# IEEE_REC_Audio_Amplifier.net
KiCad netlist of a schematic drawn in EAGLE
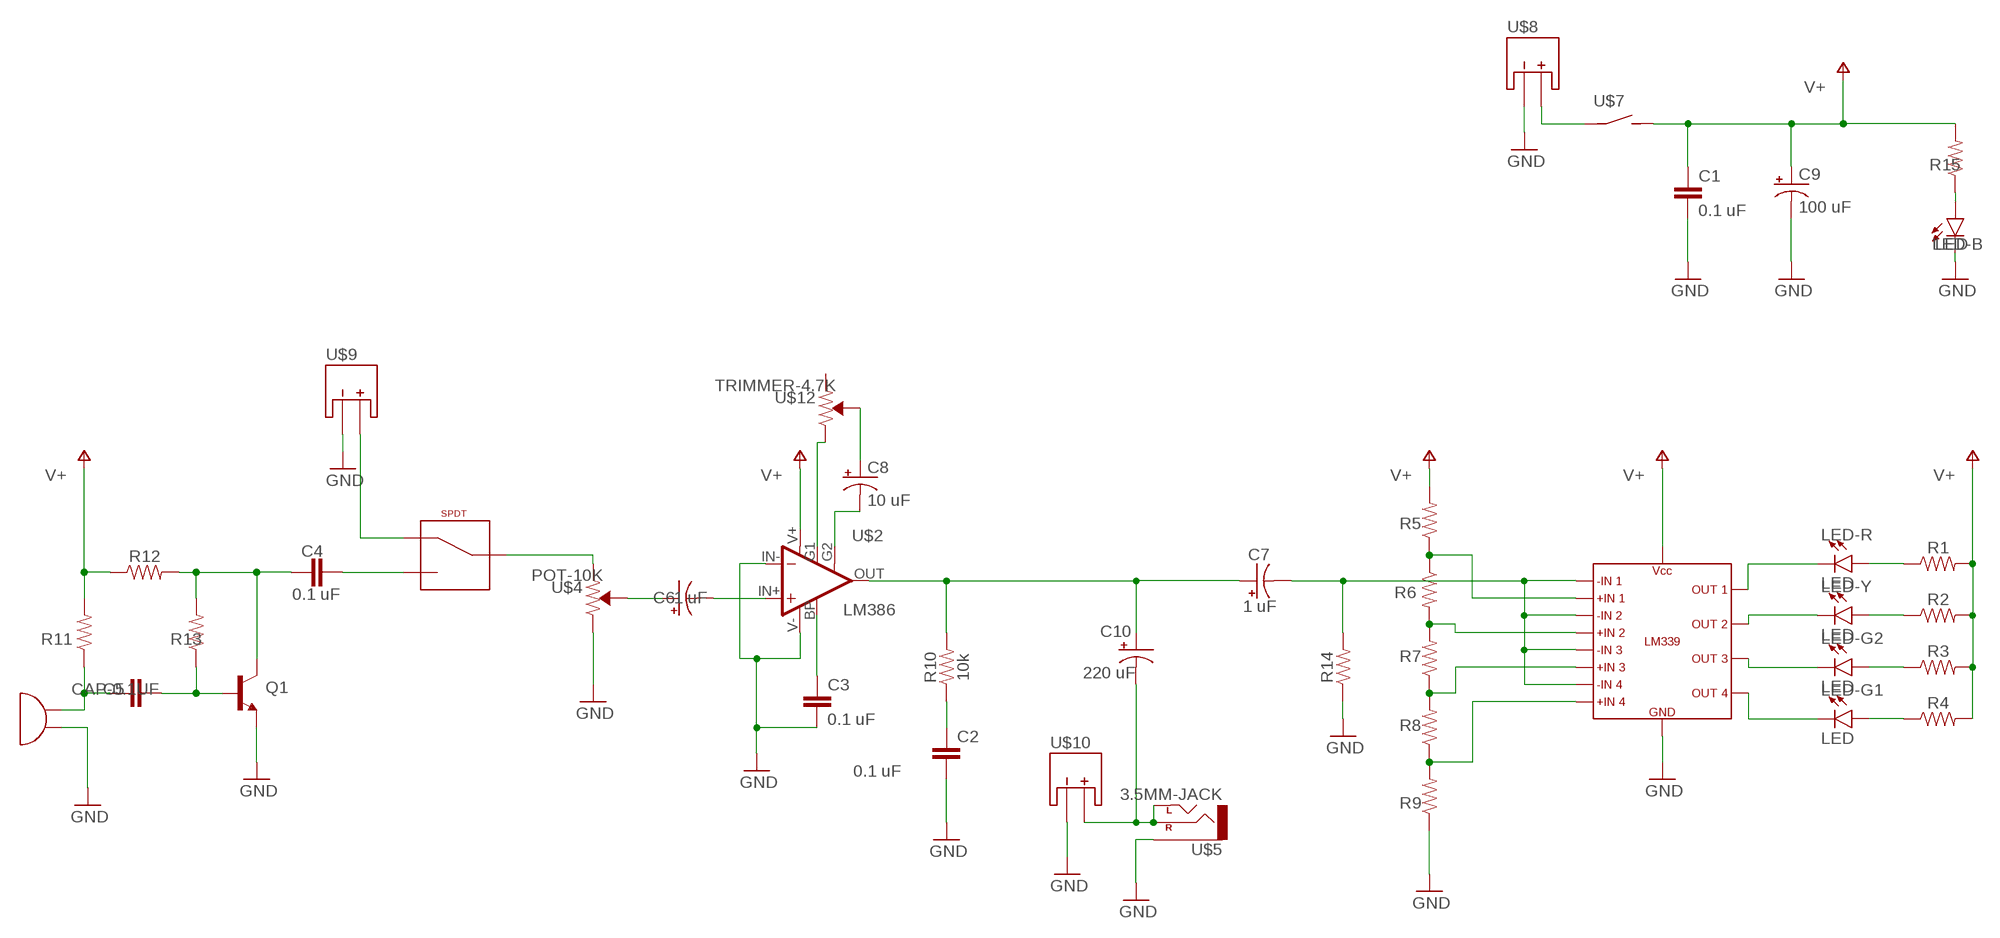
[diagram p0: schematic, sheet 1]

(export (version "E")
  (design (tool "Eeschema 10.0.6"))
  (components
    (comp (ref "C1")
      (value "0.1 uF")
      (footprint "eagle-import:CAP-PTH-SMALL-KIT")
      (libsource (lib "eagle-import") (part "CAP-0.1UF"))
    )
    (comp (ref "C2")
      (value "0.1 uF")
      (footprint "eagle-import:CAP-PTH-SMALL-KIT")
      (libsource (lib "eagle-import") (part "CAP-0.1UF"))
    )
    (comp (ref "C3")
      (value "0.1 uF")
      (footprint "eagle-import:CAP-PTH-SMALL-KIT")
      (libsource (lib "eagle-import") (part "CAP-0.1UF"))
    )
    (comp (ref "C4")
      (value "0.1 uF")
      (footprint "eagle-import:CAP-PTH-SMALL-KIT")
      (libsource (lib "eagle-import") (part "CAP-0.1UF"))
    )
    (comp (ref "C5")
      (value "CAP-0.1UF")
      (footprint "eagle-import:CAP-PTH-SMALL-KIT")
      (libsource (lib "eagle-import") (part "CAP-0.1UF"))
    )
    (comp (ref "C6")
      (value "1 uF")
      (footprint "eagle-import:CPOL-RADIAL-2.5MM-5.2MM")
      (libsource (lib "eagle-import") (part "CAP-1UF"))
    )
    (comp (ref "C7")
      (value "1 uF")
      (footprint "eagle-import:CPOL-RADIAL-2.5MM-5.2MM")
      (libsource (lib "eagle-import") (part "CAP-1UF"))
    )
    (comp (ref "C8")
      (value "10 uF")
      (footprint "eagle-import:CPOL-RADIAL-2.5MM-5.2MM")
      (libsource (lib "eagle-import") (part "CAP-10UF"))
    )
    (comp (ref "C9")
      (value "100 uF")
      (footprint "eagle-import:CPOL-RADIAL-2.5MM-6.5MM")
      (libsource (lib "eagle-import") (part "CAP-100UF"))
    )
    (comp (ref "C10")
      (value "220 uF")
      (footprint "eagle-import:CPOL-RADIAL-2.5MM-8.1MM")
      (libsource (lib "eagle-import") (part "CAP-220UF"))
    )
    (comp (ref "LED-B")
      (value "LED")
      (footprint "eagle-import:LED_5MM-KIT")
      (libsource (lib "eagle-import") (part "LED"))
    )
    (comp (ref "LED-G1")
      (value "LED")
      (footprint "eagle-import:LED_5MM-KIT")
      (libsource (lib "eagle-import") (part "LED"))
    )
    (comp (ref "LED-G2")
      (value "LED")
      (footprint "eagle-import:LED_5MM-KIT")
      (libsource (lib "eagle-import") (part "LED"))
    )
    (comp (ref "LED-R")
      (value "LED")
      (footprint "eagle-import:LED_5MM-KIT")
      (libsource (lib "eagle-import") (part "LED"))
    )
    (comp (ref "LED-Y")
      (value "LED")
      (footprint "eagle-import:LED_5MM-KIT")
      (libsource (lib "eagle-import") (part "LED"))
    )
    (comp (ref "Q1")
      (value "2N3904")
      (footprint "eagle-import:TO92-CBE")
      (libsource (lib "eagle-import") (part "2N3904"))
    )
    (comp (ref "R1")
      (value "470")
      (footprint "eagle-import:AXIAL-0.3-KIT")
      (libsource (lib "eagle-import") (part "RESISTOR"))
    )
    (comp (ref "R2")
      (value "RESISTOR")
      (footprint "eagle-import:AXIAL-0.3-KIT")
      (libsource (lib "eagle-import") (part "RESISTOR"))
    )
    (comp (ref "R3")
      (value "RESISTOR")
      (footprint "eagle-import:AXIAL-0.3-KIT")
      (libsource (lib "eagle-import") (part "RESISTOR"))
    )
    (comp (ref "R4")
      (value "RESISTOR")
      (footprint "eagle-import:AXIAL-0.3-KIT")
      (libsource (lib "eagle-import") (part "RESISTOR"))
    )
    (comp (ref "R5")
      (value "RESISTOR")
      (footprint "eagle-import:AXIAL-0.3-KIT")
      (libsource (lib "eagle-import") (part "RESISTOR"))
    )
    (comp (ref "R6")
      (value "RESISTOR")
      (footprint "eagle-import:AXIAL-0.3-KIT")
      (libsource (lib "eagle-import") (part "RESISTOR"))
    )
    (comp (ref "R7")
      (value "RESISTOR")
      (footprint "eagle-import:AXIAL-0.3-KIT")
      (libsource (lib "eagle-import") (part "RESISTOR"))
    )
    (comp (ref "R8")
      (value "RESISTOR")
      (footprint "eagle-import:AXIAL-0.3-KIT")
      (libsource (lib "eagle-import") (part "RESISTOR"))
    )
    (comp (ref "R9")
      (value "RESISTOR")
      (footprint "eagle-import:AXIAL-0.3-KIT")
      (libsource (lib "eagle-import") (part "RESISTOR"))
    )
    (comp (ref "R10")
      (value "10k")
      (footprint "eagle-import:AXIAL-0.3-KIT")
      (libsource (lib "eagle-import") (part "RESISTOR"))
    )
    (comp (ref "R11")
      (value "RESISTOR")
      (footprint "eagle-import:AXIAL-0.3-KIT")
      (libsource (lib "eagle-import") (part "RESISTOR"))
    )
    (comp (ref "R12")
      (value "RESISTOR")
      (footprint "eagle-import:AXIAL-0.3-KIT")
      (libsource (lib "eagle-import") (part "RESISTOR"))
    )
    (comp (ref "R13")
      (value "RESISTOR")
      (footprint "eagle-import:AXIAL-0.3-KIT")
      (libsource (lib "eagle-import") (part "RESISTOR"))
    )
    (comp (ref "R14")
      (value "RESISTOR")
      (footprint "eagle-import:AXIAL-0.3-KIT")
      (libsource (lib "eagle-import") (part "RESISTOR"))
    )
    (comp (ref "R15")
      (value "RESISTOR")
      (footprint "eagle-import:AXIAL-0.3-KIT")
      (libsource (lib "eagle-import") (part "RESISTOR"))
    )
    (comp (ref "U$1")
      (value "SPDT")
      (footprint "eagle-import:OS102011MA1QN1")
      (libsource (lib "eagle-import") (part "SPDT"))
    )
    (comp (ref "U$2")
      (value "LM386")
      (footprint "eagle-import:DIL08")
      (libsource (lib "eagle-import") (part "LM386"))
    )
    (comp (ref "U$3")
      (value "LM339")
      (footprint "eagle-import:DIL14")
      (libsource (lib "eagle-import") (part "LM339"))
    )
    (comp (ref "U$4")
      (value "POT-10K")
      (footprint "eagle-import:PTV09-SERIES")
      (libsource (lib "eagle-import") (part "POT-10K"))
    )
    (comp (ref "U$5")
      (value "3.5MM-JACK")
      (footprint "eagle-import:SJ1-352XN")
      (libsource (lib "eagle-import") (part "3.5MM-JACK"))
    )
    (comp (ref "U$6")
      (value "MIC")
      (footprint "eagle-import:MIC")
      (libsource (lib "eagle-import") (part "MIC"))
    )
    (comp (ref "U$7")
      (value "SPST")
      (footprint "eagle-import:TMS6T1B1M1QE")
      (libsource (lib "eagle-import") (part "SPST"))
    )
    (comp (ref "U$8")
      (value "2PIN-CONNECTOR")
      (footprint "eagle-import:2PIN-CONN")
      (libsource (lib "eagle-import") (part "2PIN-CONNECTOR"))
    )
    (comp (ref "U$9")
      (value "2PIN-CONNECTOR")
      (footprint "eagle-import:2PIN-CONN")
      (libsource (lib "eagle-import") (part "2PIN-CONNECTOR"))
    )
    (comp (ref "U$10")
      (value "2PIN-CONNECTOR")
      (footprint "eagle-import:2PIN-CONN")
      (libsource (lib "eagle-import") (part "2PIN-CONNECTOR"))
    )
    (comp (ref "U$12")
      (value "TRIMMER-4.7K")
      (footprint "eagle-import:CB10MV472ME")
      (libsource (lib "eagle-import") (part "TRIMMER-4.7K"))
    )
  )
  (nets
    (net (code "1") (name "GND") (class "Default")
      (node (ref "C1") (pin "2") (pinfunction "2_2") (pintype "passive"))
      (node (ref "C2") (pin "2") (pinfunction "2_2") (pintype "passive"))
      (node (ref "C3") (pin "2") (pinfunction "2_2") (pintype "passive"))
      (node (ref "C9") (pin "-") (pinfunction "-_-") (pintype "passive"))
      (node (ref "LED-B") (pin "-") (pinfunction "C_-") (pintype "passive"))
      (node (ref "Q1") (pin "E") (pinfunction "E_E") (pintype "passive"))
      (node (ref "R14") (pin "P$1") (pinfunction "1_P$1") (pintype "passive"))
      (node (ref "R9") (pin "P$1") (pinfunction "1_P$1") (pintype "passive"))
      (node (ref "U$10") (pin "-") (pinfunction "-_-") (pintype "bidirectional"))
      (node (ref "U$2") (pin "IN-") (pinfunction "-IN_IN-") (pintype "input"))
      (node (ref "U$2") (pin "V-") (pinfunction "V-_V-") (pintype "power_in"))
      (node (ref "U$3") (pin "P$12") (pinfunction "P12_P$12") (pintype "bidirectional"))
      (node (ref "U$4") (pin "P$3") (pinfunction "CW_P$3") (pintype "passive"))
      (node (ref "U$5") (pin "P$1") (pinfunction "SLEEVE_P$1") (pintype "bidirectional"))
      (node (ref "U$6") (pin "-") (pinfunction "P$1_-") (pintype "bidirectional"))
      (node (ref "U$8") (pin "-") (pinfunction "-_-") (pintype "bidirectional"))
      (node (ref "U$9") (pin "-") (pinfunction "-_-") (pintype "bidirectional"))
    )
    (net (code "2") (name "Net-(C3-Pad1)") (class "Default")
      (node (ref "C3") (pin "1") (pinfunction "1_1") (pintype "passive"))
      (node (ref "U$2") (pin "BP") (pinfunction "BP_BP") (pintype "bidirectional"))
    )
    (net (code "3") (name "Net-(C4-Pad2)") (class "Default")
      (node (ref "C4") (pin "2") (pinfunction "2_2") (pintype "passive"))
      (node (ref "U$1") (pin "P$3") (pinfunction "P$3_P$3") (pintype "bidirectional"))
    )
    (net (code "4") (name "Net-(C8-Pad-)") (class "Default")
      (node (ref "C8") (pin "-") (pinfunction "-_-") (pintype "passive"))
      (node (ref "U$2") (pin "G2") (pinfunction "GAIN_G2") (pintype "bidirectional"))
    )
    (net (code "5") (name "Net-(LED-B-A)") (class "Default")
      (node (ref "LED-B") (pin "+") (pinfunction "A_+") (pintype "passive"))
      (node (ref "R15") (pin "P$1") (pinfunction "1_P$1") (pintype "passive"))
    )
    (net (code "6") (name "Net-(LED-G1-A)") (class "Default")
      (node (ref "LED-G1") (pin "+") (pinfunction "A_+") (pintype "passive"))
      (node (ref "R4") (pin "P$1") (pinfunction "1_P$1") (pintype "passive"))
    )
    (net (code "7") (name "Net-(LED-G1-C)") (class "Default")
      (node (ref "LED-G1") (pin "-") (pinfunction "C_-") (pintype "passive"))
      (node (ref "U$3") (pin "P$13") (pinfunction "P13_P$13") (pintype "bidirectional"))
    )
    (net (code "8") (name "Net-(LED-G2-A)") (class "Default")
      (node (ref "LED-G2") (pin "+") (pinfunction "A_+") (pintype "passive"))
      (node (ref "R3") (pin "P$1") (pinfunction "1_P$1") (pintype "passive"))
    )
    (net (code "9") (name "Net-(LED-G2-C)") (class "Default")
      (node (ref "LED-G2") (pin "-") (pinfunction "C_-") (pintype "passive"))
      (node (ref "U$3") (pin "P$14") (pinfunction "P14_P$14") (pintype "bidirectional"))
    )
    (net (code "10") (name "Net-(LED-R-A)") (class "Default")
      (node (ref "LED-R") (pin "+") (pinfunction "A_+") (pintype "passive"))
      (node (ref "R1") (pin "P$1") (pinfunction "1_P$1") (pintype "passive"))
    )
    (net (code "11") (name "Net-(LED-R-C)") (class "Default")
      (node (ref "LED-R") (pin "-") (pinfunction "C_-") (pintype "passive"))
      (node (ref "U$3") (pin "P$1") (pinfunction "P1_P$1") (pintype "bidirectional"))
    )
    (net (code "12") (name "Net-(LED-Y-A)") (class "Default")
      (node (ref "LED-Y") (pin "+") (pinfunction "A_+") (pintype "passive"))
      (node (ref "R2") (pin "P$1") (pinfunction "1_P$1") (pintype "passive"))
    )
    (net (code "13") (name "Net-(LED-Y-C)") (class "Default")
      (node (ref "LED-Y") (pin "-") (pinfunction "C_-") (pintype "passive"))
      (node (ref "U$3") (pin "P$2") (pinfunction "P2_P$2") (pintype "bidirectional"))
    )
    (net (code "14") (name "Net-(R5-1)") (class "Default")
      (node (ref "R5") (pin "P$1") (pinfunction "1_P$1") (pintype "passive"))
      (node (ref "R6") (pin "P$1") (pinfunction "1_P$1") (pintype "passive"))
      (node (ref "U$3") (pin "P$7") (pinfunction "P7_P$7") (pintype "bidirectional"))
    )
    (net (code "15") (name "Net-(R6-2)") (class "Default")
      (node (ref "R6") (pin "P$2") (pinfunction "2_P$2") (pintype "passive"))
      (node (ref "R7") (pin "P$2") (pinfunction "2_P$2") (pintype "passive"))
      (node (ref "U$3") (pin "P$5") (pinfunction "P5_P$5") (pintype "bidirectional"))
    )
    (net (code "16") (name "Net-(R7-1)") (class "Default")
      (node (ref "R7") (pin "P$1") (pinfunction "1_P$1") (pintype "passive"))
      (node (ref "R8") (pin "P$2") (pinfunction "2_P$2") (pintype "passive"))
      (node (ref "U$3") (pin "P$9") (pinfunction "P9_P$9") (pintype "bidirectional"))
    )
    (net (code "17") (name "Net-(R8-1)") (class "Default")
      (node (ref "R8") (pin "P$1") (pinfunction "1_P$1") (pintype "passive"))
      (node (ref "R9") (pin "P$2") (pinfunction "2_P$2") (pintype "passive"))
      (node (ref "U$3") (pin "P$11") (pinfunction "P11_P$11") (pintype "bidirectional"))
    )
    (net (code "18") (name "Net-(R10-1)") (class "Default")
      (node (ref "C2") (pin "1") (pinfunction "1_1") (pintype "passive"))
      (node (ref "R10") (pin "P$1") (pinfunction "1_P$1") (pintype "passive"))
    )
    (net (code "19") (name "Net-(R10-2)") (class "Default")
      (node (ref "C10") (pin "+") (pinfunction "+_+") (pintype "passive"))
      (node (ref "C7") (pin "+") (pinfunction "+_+") (pintype "passive"))
      (node (ref "R10") (pin "P$2") (pinfunction "2_P$2") (pintype "passive"))
      (node (ref "U$2") (pin "OUT") (pinfunction "OUT_OUT") (pintype "output"))
    )
    (net (code "20") (name "Net-(R11-1)") (class "Default")
      (node (ref "C5") (pin "1") (pinfunction "1_1") (pintype "passive"))
      (node (ref "R11") (pin "P$1") (pinfunction "1_P$1") (pintype "passive"))
      (node (ref "U$6") (pin "+") (pinfunction "P$2_+") (pintype "bidirectional"))
    )
    (net (code "21") (name "Net-(R12-2)") (class "Default")
      (node (ref "C4") (pin "1") (pinfunction "1_1") (pintype "passive"))
      (node (ref "Q1") (pin "C") (pinfunction "C_C") (pintype "passive"))
      (node (ref "R12") (pin "P$2") (pinfunction "2_P$2") (pintype "passive"))
      (node (ref "R13") (pin "P$2") (pinfunction "2_P$2") (pintype "passive"))
    )
    (net (code "22") (name "Net-(R13-1)") (class "Default")
      (node (ref "C5") (pin "2") (pinfunction "2_2") (pintype "passive"))
      (node (ref "Q1") (pin "B") (pinfunction "B_B") (pintype "passive"))
      (node (ref "R13") (pin "P$1") (pinfunction "1_P$1") (pintype "passive"))
    )
    (net (code "23") (name "Net-(R14-2)") (class "Default")
      (node (ref "C7") (pin "-") (pinfunction "-_-") (pintype "passive"))
      (node (ref "R14") (pin "P$2") (pinfunction "2_P$2") (pintype "passive"))
      (node (ref "U$3") (pin "P$10") (pinfunction "P10_P$10") (pintype "bidirectional"))
      (node (ref "U$3") (pin "P$4") (pinfunction "P4_P$4") (pintype "bidirectional"))
      (node (ref "U$3") (pin "P$6") (pinfunction "P6_P$6") (pintype "bidirectional"))
      (node (ref "U$3") (pin "P$8") (pinfunction "P8_P$8") (pintype "bidirectional"))
    )
    (net (code "24") (name "Net-(U$1-PadP$1)") (class "Default")
      (node (ref "U$1") (pin "P$1") (pinfunction "P$1_P$1") (pintype "bidirectional"))
      (node (ref "U$9") (pin "+") (pinfunction "+_+") (pintype "bidirectional"))
    )
    (net (code "25") (name "Net-(U$2-+IN)") (class "Default")
      (node (ref "C6") (pin "-") (pinfunction "-_-") (pintype "passive"))
      (node (ref "U$2") (pin "IN+") (pinfunction "+IN_IN+") (pintype "input"))
    )
    (net (code "26") (name "Net-(U$4-CCW)") (class "Default")
      (node (ref "U$1") (pin "P$2") (pinfunction "P$2_P$2") (pintype "bidirectional"))
      (node (ref "U$4") (pin "P$1") (pinfunction "CCW_P$1") (pintype "passive"))
    )
    (net (code "27") (name "Net-(U$4-WIPER)") (class "Default")
      (node (ref "C6") (pin "+") (pinfunction "+_+") (pintype "passive"))
      (node (ref "U$4") (pin "P$2") (pinfunction "WIPER_P$2") (pintype "passive"))
    )
    (net (code "28") (name "Net-(U$5-LEFT)") (class "Default")
      (node (ref "C10") (pin "-") (pinfunction "-_-") (pintype "passive"))
      (node (ref "U$10") (pin "+") (pinfunction "+_+") (pintype "bidirectional"))
      (node (ref "U$5") (pin "P$2") (pinfunction "RIGHT_P$2") (pintype "bidirectional"))
      (node (ref "U$5") (pin "P$3") (pinfunction "LEFT_P$3") (pintype "bidirectional"))
    )
    (net (code "29") (name "Net-(U$7-P)") (class "Default")
      (node (ref "U$7") (pin "+") (pinfunction "P_+") (pintype "passive"))
      (node (ref "U$8") (pin "+") (pinfunction "+_+") (pintype "bidirectional"))
    )
    (net (code "30") (name "Net-(U$12-CW)") (class "Default")
      (node (ref "U$12") (pin "P$3") (pinfunction "CW_P$3") (pintype "passive"))
      (node (ref "U$2") (pin "G1") (pinfunction "GAIN_G1") (pintype "bidirectional"))
    )
    (net (code "31") (name "Net-(U$12-WIPER)") (class "Default")
      (node (ref "C8") (pin "+") (pinfunction "+_+") (pintype "passive"))
      (node (ref "U$12") (pin "P$2") (pinfunction "WIPER_P$2") (pintype "passive"))
    )
    (net (code "32") (name "V+") (class "Default")
      (node (ref "C1") (pin "1") (pinfunction "1_1") (pintype "passive"))
      (node (ref "C9") (pin "+") (pinfunction "+_+") (pintype "passive"))
      (node (ref "R1") (pin "P$2") (pinfunction "2_P$2") (pintype "passive"))
      (node (ref "R11") (pin "P$2") (pinfunction "2_P$2") (pintype "passive"))
      (node (ref "R12") (pin "P$1") (pinfunction "1_P$1") (pintype "passive"))
      (node (ref "R15") (pin "P$2") (pinfunction "2_P$2") (pintype "passive"))
      (node (ref "R2") (pin "P$2") (pinfunction "2_P$2") (pintype "passive"))
      (node (ref "R3") (pin "P$2") (pinfunction "2_P$2") (pintype "passive"))
      (node (ref "R4") (pin "P$2") (pinfunction "2_P$2") (pintype "passive"))
      (node (ref "R5") (pin "P$2") (pinfunction "2_P$2") (pintype "passive"))
      (node (ref "U$2") (pin "V+") (pinfunction "V+_V+") (pintype "power_in"))
      (node (ref "U$3") (pin "P$3") (pinfunction "P3_P$3") (pintype "bidirectional"))
      (node (ref "U$7") (pin "-") (pinfunction "S_-") (pintype "passive"))
    )
    (net (code "33") (name "unconnected-(U$12-CCW-PadP$1)") (class "Default")
      (node (ref "U$12") (pin "P$1") (pinfunction "CCW_P$1") (pintype "passive"))
    )
  )
)
